# oLoRa-part-MainMCU.net
KiCad netlist of a schematic drawn in EasyEDA
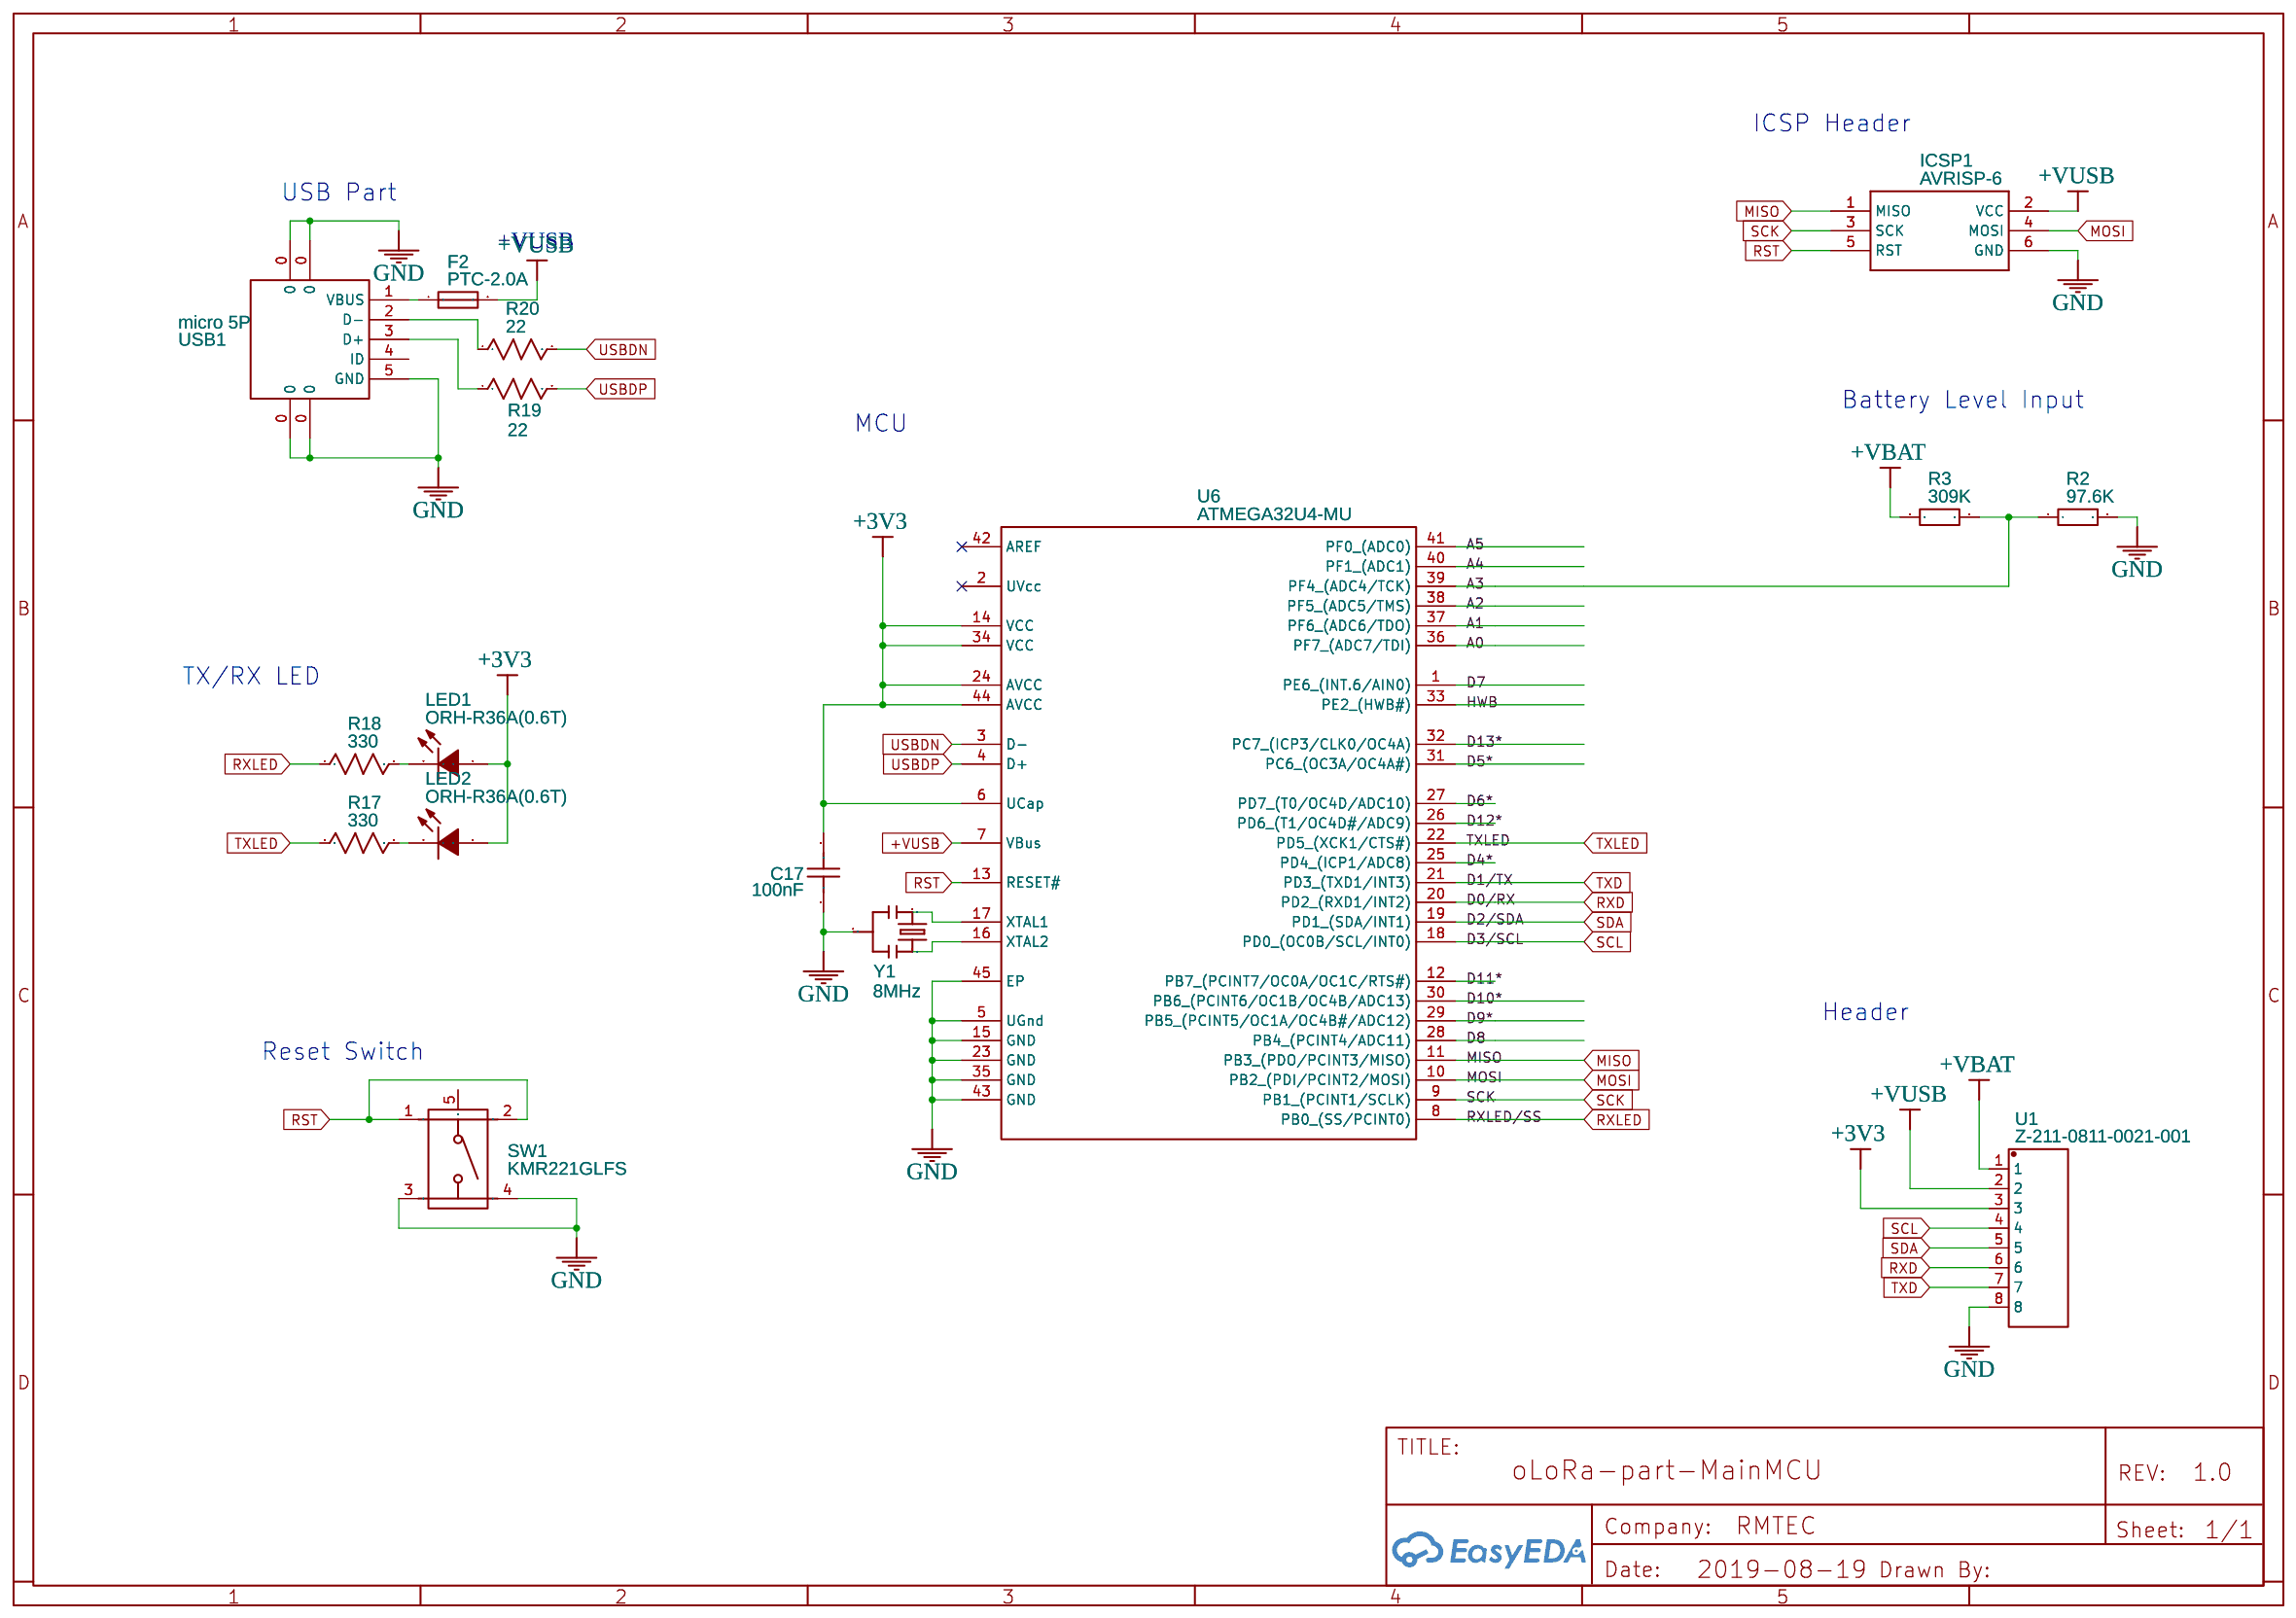
[diagram p0: schematic sheet]

(export (version "E")
  (design (tool "Eeschema 10.0.6"))
  (components
    (comp (ref "C17")
      (value "100nF")
      (fields
        (field (name "BOM_Manufacturer Part") "CC0603KRX7R9BB104")
        (field (name "BOM_Supplier Part") "C14663")
      )
      (libsource (lib "") (part "CC0603KRX7R9BB104"))
    )
    (comp (ref "F2")
      (value "PTC-2.0A")
      (fields
        (field (name "BOM_Manufacturer Part") "MF-MSMF200-2")
        (field (name "BOM_Supplier Part") "C210837")
      )
      (libsource (lib "") (part "Unknown_225_145"))
    )
    (comp (ref "ICSP1")
      (value "AVRISP-6")
      (fields (field (name "BOM_Manufacturer Part") "?"))
      (libsource (lib "") (part "Unknown_970_110"))
    )
    (comp (ref "LED1")
      (value "ORH-R36A(0.6T)")
      (fields (field (name "BOM_Supplier Part") "C205445"))
      (libsource (lib "") (part "Unknown_220_380"))
    )
    (comp (ref "LED2")
      (value "ORH-R36A(0.6T)")
      (fields (field (name "BOM_Supplier Part") "C205445"))
      (libsource (lib "") (part "Unknown_220_420"))
    )
    (comp (ref "R2")
      (value "97.6K")
      (fields
        (field (name "BOM_Manufacturer Part") "CR0603-FX-9762ELF")
        (field (name "BOM_Supplier Part") "C203901")
      )
      (libsource (lib "") (part "CR0603-FX-9762ELF"))
    )
    (comp (ref "R3")
      (value "309K")
      (fields
        (field (name "BOM_Manufacturer Part") "0603WAF3093T5E")
        (field (name "BOM_Supplier Part") "C23001")
      )
      (libsource (lib "") (part "0603WAF3093T5E"))
    )
    (comp (ref "R17") (value "330") (libsource (lib "") (part "Res_0603(1/10W)_US")))
    (comp (ref "R18") (value "330") (libsource (lib "") (part "Res_0603(1/10W)_US")))
    (comp (ref "R19") (value "22") (libsource (lib "") (part "Res_0603(1/10W)_US")))
    (comp (ref "R20") (value "22") (libsource (lib "") (part "Res_0603(1/10W)_US")))
    (comp (ref "SW1")
      (value "KMR221GLFS")
      (fields (field (name "BOM_Supplier Part") "C72443"))
      (libsource (lib "") (part "Unknown_225_575"))
    )
    (comp (ref "U1")
      (value "Z-211-0811-0021-001")
      (fields (field (name "BOM_Supplier Part") "C190820"))
      (libsource (lib "") (part "Unknown_1020_620"))
    )
    (comp (ref "U6")
      (value "ATMEGA32U4-MU")
      (fields (field (name "BOM_Supplier Part") "C112161"))
      (libsource (lib "") (part "Unknown_610_420"))
    )
    (comp (ref "USB1")
      (value "micro 5P")
      (fields (field (name "BOM_Supplier Part") "C77238"))
      (libsource (lib "") (part "Unknown_160_165"))
    )
    (comp (ref "Y1")
      (value "8MHz")
      (fields (field (name "BOM_Manufacturer Part") "CSTCE8M00G55-R0"))
      (libsource (lib "") (part "Unknown_455_465"))
    )
  )
  (nets
    (net (code "1") (name "+3V3") (class "Default")
      (node (ref "C17") (pin "2") (pinfunction "2_2") (pintype "unspecified"))
      (node (ref "LED1") (pin "1") (pinfunction "A_1") (pintype "unspecified"))
      (node (ref "LED2") (pin "1") (pinfunction "A_1") (pintype "unspecified"))
      (node (ref "U1") (pin "3") (pinfunction "3_3") (pintype "unspecified"))
      (node (ref "U6") (pin "14") (pinfunction "VCC_14") (pintype "passive"))
      (node (ref "U6") (pin "24") (pinfunction "AVCC_24") (pintype "passive"))
      (node (ref "U6") (pin "34") (pinfunction "VCC_34") (pintype "passive"))
      (node (ref "U6") (pin "44") (pinfunction "AVCC_44") (pintype "passive"))
      (node (ref "U6") (pin "6") (pinfunction "UCap_6") (pintype "unspecified"))
    )
    (net (code "2") (name "+VBAT") (class "Default")
      (node (ref "R3") (pin "1") (pinfunction "1_1") (pintype "input"))
      (node (ref "U1") (pin "1") (pinfunction "1_1") (pintype "unspecified"))
    )
    (net (code "3") (name "+VUSB") (class "Default")
      (node (ref "F2") (pin "2") (pinfunction "2_2") (pintype "unspecified"))
      (node (ref "ICSP1") (pin "2") (pinfunction "VCC_2") (pintype "passive"))
      (node (ref "U1") (pin "2") (pinfunction "2_2") (pintype "unspecified"))
      (node (ref "U6") (pin "7") (pinfunction "VBus_7") (pintype "unspecified"))
    )
    (net (code "4") (name "/A0") (class "Default")
      (node (ref "U6") (pin "36") (pinfunction "PF7_(ADC7/TDI)_36") (pintype "bidirectional"))
    )
    (net (code "5") (name "/A1") (class "Default")
      (node (ref "U6") (pin "37") (pinfunction "PF6_(ADC6/TDO)_37") (pintype "bidirectional"))
    )
    (net (code "6") (name "/A2") (class "Default")
      (node (ref "U6") (pin "38") (pinfunction "PF5_(ADC5/TMS)_38") (pintype "bidirectional"))
    )
    (net (code "7") (name "/A3") (class "Default")
      (node (ref "R2") (pin "1") (pinfunction "1_1") (pintype "unspecified"))
      (node (ref "R3") (pin "2") (pinfunction "2_2") (pintype "input"))
      (node (ref "U6") (pin "39") (pinfunction "PF4_(ADC4/TCK)_39") (pintype "bidirectional"))
    )
    (net (code "8") (name "/A4") (class "Default")
      (node (ref "U6") (pin "40") (pinfunction "PF1_(ADC1)_40") (pintype "bidirectional"))
    )
    (net (code "9") (name "/A5") (class "Default")
      (node (ref "U6") (pin "41") (pinfunction "PF0_(ADC0)_41") (pintype "bidirectional"))
    )
    (net (code "10") (name "/D4*") (class "Default")
      (node (ref "U6") (pin "25") (pinfunction "PD4_(ICP1/ADC8)_25") (pintype "bidirectional"))
    )
    (net (code "11") (name "/D5*") (class "Default")
      (node (ref "U6") (pin "31") (pinfunction "PC6_(OC3A/OC4A#)_31") (pintype "bidirectional"))
    )
    (net (code "12") (name "/D6*") (class "Default")
      (node (ref "U6") (pin "27") (pinfunction "PD7_(T0/OC4D/ADC10)_27") (pintype "bidirectional"))
    )
    (net (code "13") (name "/D7") (class "Default")
      (node (ref "U6") (pin "1") (pinfunction "PE6_(INT.6/AIN0)_1") (pintype "bidirectional"))
    )
    (net (code "14") (name "/D8") (class "Default")
      (node (ref "U6") (pin "28") (pinfunction "PB4_(PCINT4/ADC11)_28") (pintype "bidirectional"))
    )
    (net (code "15") (name "/D9*") (class "Default")
      (node (ref "U6") (pin "29") (pinfunction "PB5_(PCINT5/OC1A/OC4B#/ADC12)_29") (pintype "bidirectional"))
    )
    (net (code "16") (name "/D10*") (class "Default")
      (node (ref "U6") (pin "30") (pinfunction "PB6_(PCINT6/OC1B/OC4B/ADC13)_30") (pintype "bidirectional"))
    )
    (net (code "17") (name "/D11*") (class "Default")
      (node (ref "U6") (pin "12") (pinfunction "PB7_(PCINT7/OC0A/OC1C/RTS#)_12") (pintype "bidirectional"))
    )
    (net (code "18") (name "/D12*") (class "Default")
      (node (ref "U6") (pin "26") (pinfunction "PD6_(T1/OC4D#/ADC9)_26") (pintype "bidirectional"))
    )
    (net (code "19") (name "/D13*") (class "Default")
      (node (ref "U6") (pin "32") (pinfunction "PC7_(ICP3/CLK0/OC4A)_32") (pintype "bidirectional"))
    )
    (net (code "20") (name "/HWB") (class "Default")
      (node (ref "U6") (pin "33") (pinfunction "PE2_(HWB#)_33") (pintype "bidirectional"))
    )
    (net (code "21") (name "GND") (class "Default")
      (node (ref "C17") (pin "1") (pinfunction "1_1") (pintype "unspecified"))
      (node (ref "ICSP1") (pin "6") (pinfunction "GND_6") (pintype "passive"))
      (node (ref "R2") (pin "2") (pinfunction "2_2") (pintype "unspecified"))
      (node (ref "SW1") (pin "3") (pinfunction "3_3") (pintype "unspecified"))
      (node (ref "SW1") (pin "4") (pinfunction "4_4") (pintype "unspecified"))
      (node (ref "U1") (pin "8") (pinfunction "8_8") (pintype "unspecified"))
      (node (ref "U6") (pin "15") (pinfunction "GND_15") (pintype "passive"))
      (node (ref "U6") (pin "23") (pinfunction "GND_23") (pintype "passive"))
      (node (ref "U6") (pin "35") (pinfunction "GND_35") (pintype "passive"))
      (node (ref "U6") (pin "43") (pinfunction "GND_43") (pintype "passive"))
      (node (ref "U6") (pin "45") (pinfunction "EP_45") (pintype "output"))
      (node (ref "U6") (pin "5") (pinfunction "UGnd_5") (pintype "passive"))
      (node (ref "USB1") (pin "0") (pinfunction "0_0") (pintype "unspecified"))
      (node (ref "USB1") (pin "5") (pinfunction "GND_5") (pintype "unspecified"))
      (node (ref "Y1") (pin "2") (pinfunction "2_2") (pintype "unspecified"))
    )
    (net (code "22") (name "MISO") (class "Default")
      (node (ref "ICSP1") (pin "1") (pinfunction "MISO_1") (pintype "input"))
      (node (ref "U6") (pin "11") (pinfunction "PB3_(PDO/PCINT3/MISO)_11") (pintype "bidirectional"))
    )
    (net (code "23") (name "MOSI") (class "Default")
      (node (ref "ICSP1") (pin "4") (pinfunction "MOSI_4") (pintype "output"))
      (node (ref "U6") (pin "10") (pinfunction "PB2_(PDI/PCINT2/MOSI)_10") (pintype "bidirectional"))
    )
    (net (code "24") (name "Net-(LED1-K)") (class "Default")
      (node (ref "LED1") (pin "2") (pinfunction "K_2") (pintype "unspecified"))
      (node (ref "R18") (pin "2") (pinfunction "2_2") (pintype "unspecified"))
    )
    (net (code "25") (name "Net-(LED2-K)") (class "Default")
      (node (ref "LED2") (pin "2") (pinfunction "K_2") (pintype "unspecified"))
      (node (ref "R17") (pin "2") (pinfunction "2_2") (pintype "unspecified"))
    )
    (net (code "26") (name "Net-(U6-XTAL1)") (class "Default")
      (node (ref "U6") (pin "17") (pinfunction "XTAL1_17") (pintype "unspecified"))
      (node (ref "Y1") (pin "1") (pinfunction "1_1") (pintype "unspecified"))
    )
    (net (code "27") (name "Net-(U6-XTAL2)") (class "Default")
      (node (ref "U6") (pin "16") (pinfunction "XTAL2_16") (pintype "output"))
      (node (ref "Y1") (pin "3") (pinfunction "3_3") (pintype "unspecified"))
    )
    (net (code "28") (name "Net-(USB1-D+)") (class "Default")
      (node (ref "R19") (pin "1") (pinfunction "1_1") (pintype "unspecified"))
      (node (ref "USB1") (pin "3") (pinfunction "D+_3") (pintype "unspecified"))
    )
    (net (code "29") (name "Net-(USB1-D-)") (class "Default")
      (node (ref "R20") (pin "1") (pinfunction "1_1") (pintype "unspecified"))
      (node (ref "USB1") (pin "2") (pinfunction "D-_2") (pintype "unspecified"))
    )
    (net (code "30") (name "Net-(USB1-VBUS)") (class "Default")
      (node (ref "F2") (pin "1") (pinfunction "1_1") (pintype "unspecified"))
      (node (ref "USB1") (pin "1") (pinfunction "VBUS_1") (pintype "unspecified"))
    )
    (net (code "31") (name "RST") (class "Default")
      (node (ref "ICSP1") (pin "5") (pinfunction "RST_5") (pintype "output"))
      (node (ref "SW1") (pin "1") (pinfunction "1_1") (pintype "unspecified"))
      (node (ref "SW1") (pin "2") (pinfunction "2_2") (pintype "unspecified"))
      (node (ref "U6") (pin "13") (pinfunction "RESET#_13") (pintype "unspecified"))
    )
    (net (code "32") (name "RXD") (class "Default")
      (node (ref "U1") (pin "6") (pinfunction "6_6") (pintype "unspecified"))
      (node (ref "U6") (pin "20") (pinfunction "PD2_(RXD1/INT2)_20") (pintype "bidirectional"))
    )
    (net (code "33") (name "RXLED") (class "Default")
      (node (ref "R18") (pin "1") (pinfunction "1_1") (pintype "unspecified"))
      (node (ref "U6") (pin "8") (pinfunction "PB0_(SS/PCINT0)_8") (pintype "bidirectional"))
    )
    (net (code "34") (name "SCK") (class "Default")
      (node (ref "ICSP1") (pin "3") (pinfunction "SCK_3") (pintype "output"))
      (node (ref "U6") (pin "9") (pinfunction "PB1_(PCINT1/SCLK)_9") (pintype "bidirectional"))
    )
    (net (code "35") (name "SCL") (class "Default")
      (node (ref "U1") (pin "4") (pinfunction "4_4") (pintype "unspecified"))
      (node (ref "U6") (pin "18") (pinfunction "PD0_(OC0B/SCL/INT0)_18") (pintype "bidirectional"))
    )
    (net (code "36") (name "SDA") (class "Default")
      (node (ref "U1") (pin "5") (pinfunction "5_5") (pintype "unspecified"))
      (node (ref "U6") (pin "19") (pinfunction "PD1_(SDA/INT1)_19") (pintype "bidirectional"))
    )
    (net (code "37") (name "TXD") (class "Default")
      (node (ref "U1") (pin "7") (pinfunction "7_7") (pintype "unspecified"))
      (node (ref "U6") (pin "21") (pinfunction "PD3_(TXD1/INT3)_21") (pintype "bidirectional"))
    )
    (net (code "38") (name "TXLED") (class "Default")
      (node (ref "R17") (pin "1") (pinfunction "1_1") (pintype "unspecified"))
      (node (ref "U6") (pin "22") (pinfunction "PD5_(XCK1/CTS#)_22") (pintype "bidirectional"))
    )
    (net (code "39") (name "USBDN") (class "Default")
      (node (ref "R20") (pin "2") (pinfunction "2_2") (pintype "unspecified"))
      (node (ref "U6") (pin "3") (pinfunction "D-_3") (pintype "bidirectional"))
    )
    (net (code "40") (name "USBDP") (class "Default")
      (node (ref "R19") (pin "2") (pinfunction "2_2") (pintype "unspecified"))
      (node (ref "U6") (pin "4") (pinfunction "D+_4") (pintype "bidirectional"))
    )
    (net (code "41") (name "unconnected-(SW1-Pad5)") (class "Default")
      (node (ref "SW1") (pin "5") (pinfunction "5_5") (pintype "unspecified"))
    )
    (net (code "42") (name "unconnected-(U6-AREF-Pad42)") (class "Default")
      (node (ref "U6") (pin "42") (pinfunction "AREF_42") (pintype "unspecified+no_connect"))
    )
    (net (code "43") (name "unconnected-(U6-UVcc-Pad2)") (class "Default")
      (node (ref "U6") (pin "2") (pinfunction "UVcc_2") (pintype "passive+no_connect"))
    )
    (net (code "44") (name "unconnected-(USB1-ID-Pad4)") (class "Default")
      (node (ref "USB1") (pin "4") (pinfunction "ID_4") (pintype "unspecified"))
    )
  )
)
